# CAN_Module.net
KiCad netlist of a schematic drawn in Altium Designer
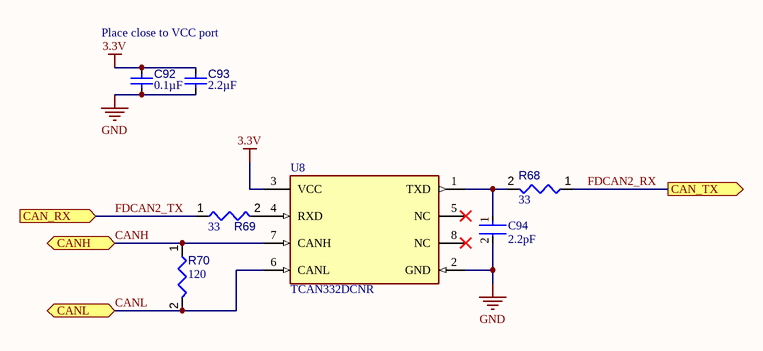
[diagram p0: CAN_Module.SchDoc]

(export (version "E")
  (design (tool "Eeschema 10.0.6"))
  (components
    (comp (ref "C92")
      (value "0.1µF")
      (footprint "CAPC0603(1608)100_L")
      (description "Chip Capacitor, 10µF +/-20%, 10V, 0603, Thickness 1 mm")
      (fields (field (name "TOLERANCE") "10%") (field (name "Comment") "Capacitor 10µF +/-20% 10V 0603"))
      (libsource (lib "Charlie's Workspace") (part "CAP-NP-2"))
    )
    (comp (ref "C93")
      (value "2.2µF")
      (footprint "CAPC0603(1608)100_L")
      (description "Chip Capacitor, 10µF +/-20%, 10V, 0603, Thickness 1 mm")
      (fields (field (name "TOLERANCE") "10%") (field (name "Comment") "Capacitor 10µF +/-20% 10V 0603"))
      (libsource (lib "Charlie's Workspace") (part "CAP-NP-2"))
    )
    (comp (ref "C94")
      (value "2.2pF")
      (footprint "FP-C0603C-CF-MFG")
      (description "C0603 2.2 pF C0G 30ppm/°C 0.25 pF 50 V")
      (fields (field (name "MANUFACTURER PART NUMBER") "C0603C229C5GACTU"))
      (libsource (lib "Altium Content Vault") (part "b4654b650e69147ec39a6b967a45e02"))
    )
    (comp (ref "R68")
      (value "33")
      (footprint "RESC1609X50X30ML08T20")
      (description "Chip Resistor, 22 Ohm, +/- 1%, 100 mW, -55 to 155 degC, 0603 (1608 Metric)")
      (fields (field (name "POWER") "100mW") (field (name "TOLERANCE") "1%"))
      (libsource (lib "Charlie's Workspace") (part "RES-2"))
    )
    (comp (ref "R69")
      (value "33")
      (footprint "RESC1609X50X30ML08T20")
      (description "Chip Resistor, 22 Ohm, +/- 1%, 100 mW, -55 to 155 degC, 0603 (1608 Metric)")
      (fields (field (name "POWER") "100mW") (field (name "TOLERANCE") "1%"))
      (libsource (lib "Charlie's Workspace") (part "RES-2"))
    )
    (comp (ref "R70")
      (value "120")
      (footprint "RESC1609X50X30ML08T20")
      (description "Chip Resistor, 20 Ohm, +/- 1%, 100 mW, -55 to 155 degC, 0603 (1608 Metric)")
      (fields (field (name "TOLERANCE") "1%") (field (name "POWER") "100mW"))
      (libsource (lib "Charlie's Workspace") (part "RES-2"))
    )
    (comp (ref "U8")
      (value "TCAN332DCNR")
      (footprint "FP-DCN0008A-IPC_A")
      (description "IC TRANSCEIVER 1/1 SOT23-8")
      (libsource (lib "Altium Content Vault") (part "adedef88f8905889a4cfcb0a070c8cc"))
    )
  )
  (nets
    (net (code "1") (name "/CANH") (class "Default")
      (node (ref "R70") (pin "1") (pinfunction "1_1") (pintype "passive"))
      (node (ref "U8") (pin "7") (pinfunction "CANH_7") (pintype "input"))
    )
    (net (code "2") (name "/CANL") (class "Default")
      (node (ref "R70") (pin "2") (pinfunction "2_2") (pintype "passive"))
      (node (ref "U8") (pin "6") (pinfunction "CANL_6") (pintype "input"))
    )
    (net (code "3") (name "/FDCAN2_RX") (class "Default")
      (node (ref "R68") (pin "1") (pinfunction "1_1") (pintype "passive"))
    )
    (net (code "4") (name "/FDCAN2_TX") (class "Default")
      (node (ref "R69") (pin "1") (pinfunction "1_1") (pintype "passive"))
    )
    (net (code "5") (name "3.3V") (class "Default")
      (node (ref "C92") (pin "1") (pinfunction "1_1") (pintype "passive"))
      (node (ref "C93") (pin "1") (pinfunction "1_1") (pintype "passive"))
      (node (ref "U8") (pin "3") (pinfunction "VCC_3") (pintype "power_in"))
    )
    (net (code "6") (name "GND") (class "Default")
      (node (ref "C92") (pin "2") (pinfunction "2_2") (pintype "passive"))
      (node (ref "C93") (pin "2") (pinfunction "2_2") (pintype "passive"))
      (node (ref "C94") (pin "2") (pinfunction "2_2") (pintype "passive"))
      (node (ref "U8") (pin "2") (pinfunction "GND_2") (pintype "input"))
    )
    (net (code "7") (name "Net-(U8-RXD)") (class "Default")
      (node (ref "R69") (pin "2") (pinfunction "2_2") (pintype "passive"))
      (node (ref "U8") (pin "4") (pinfunction "RXD_4") (pintype "input"))
    )
    (net (code "8") (name "Net-(U8-TXD)") (class "Default")
      (node (ref "C94") (pin "1") (pinfunction "1_1") (pintype "passive"))
      (node (ref "R68") (pin "2") (pinfunction "2_2") (pintype "passive"))
      (node (ref "U8") (pin "1") (pinfunction "TXD_1") (pintype "output"))
    )
    (net (code "9") (name "unconnected-(U8-NC-Pad5)") (class "Default")
      (node (ref "U8") (pin "5") (pinfunction "NC_5") (pintype "passive+no_connect"))
    )
    (net (code "10") (name "unconnected-(U8-NC-Pad8)") (class "Default")
      (node (ref "U8") (pin "8") (pinfunction "NC_8") (pintype "passive+no_connect"))
    )
  )
)
